# LedDuino.net
KiCad netlist of a schematic drawn in Altium Designer
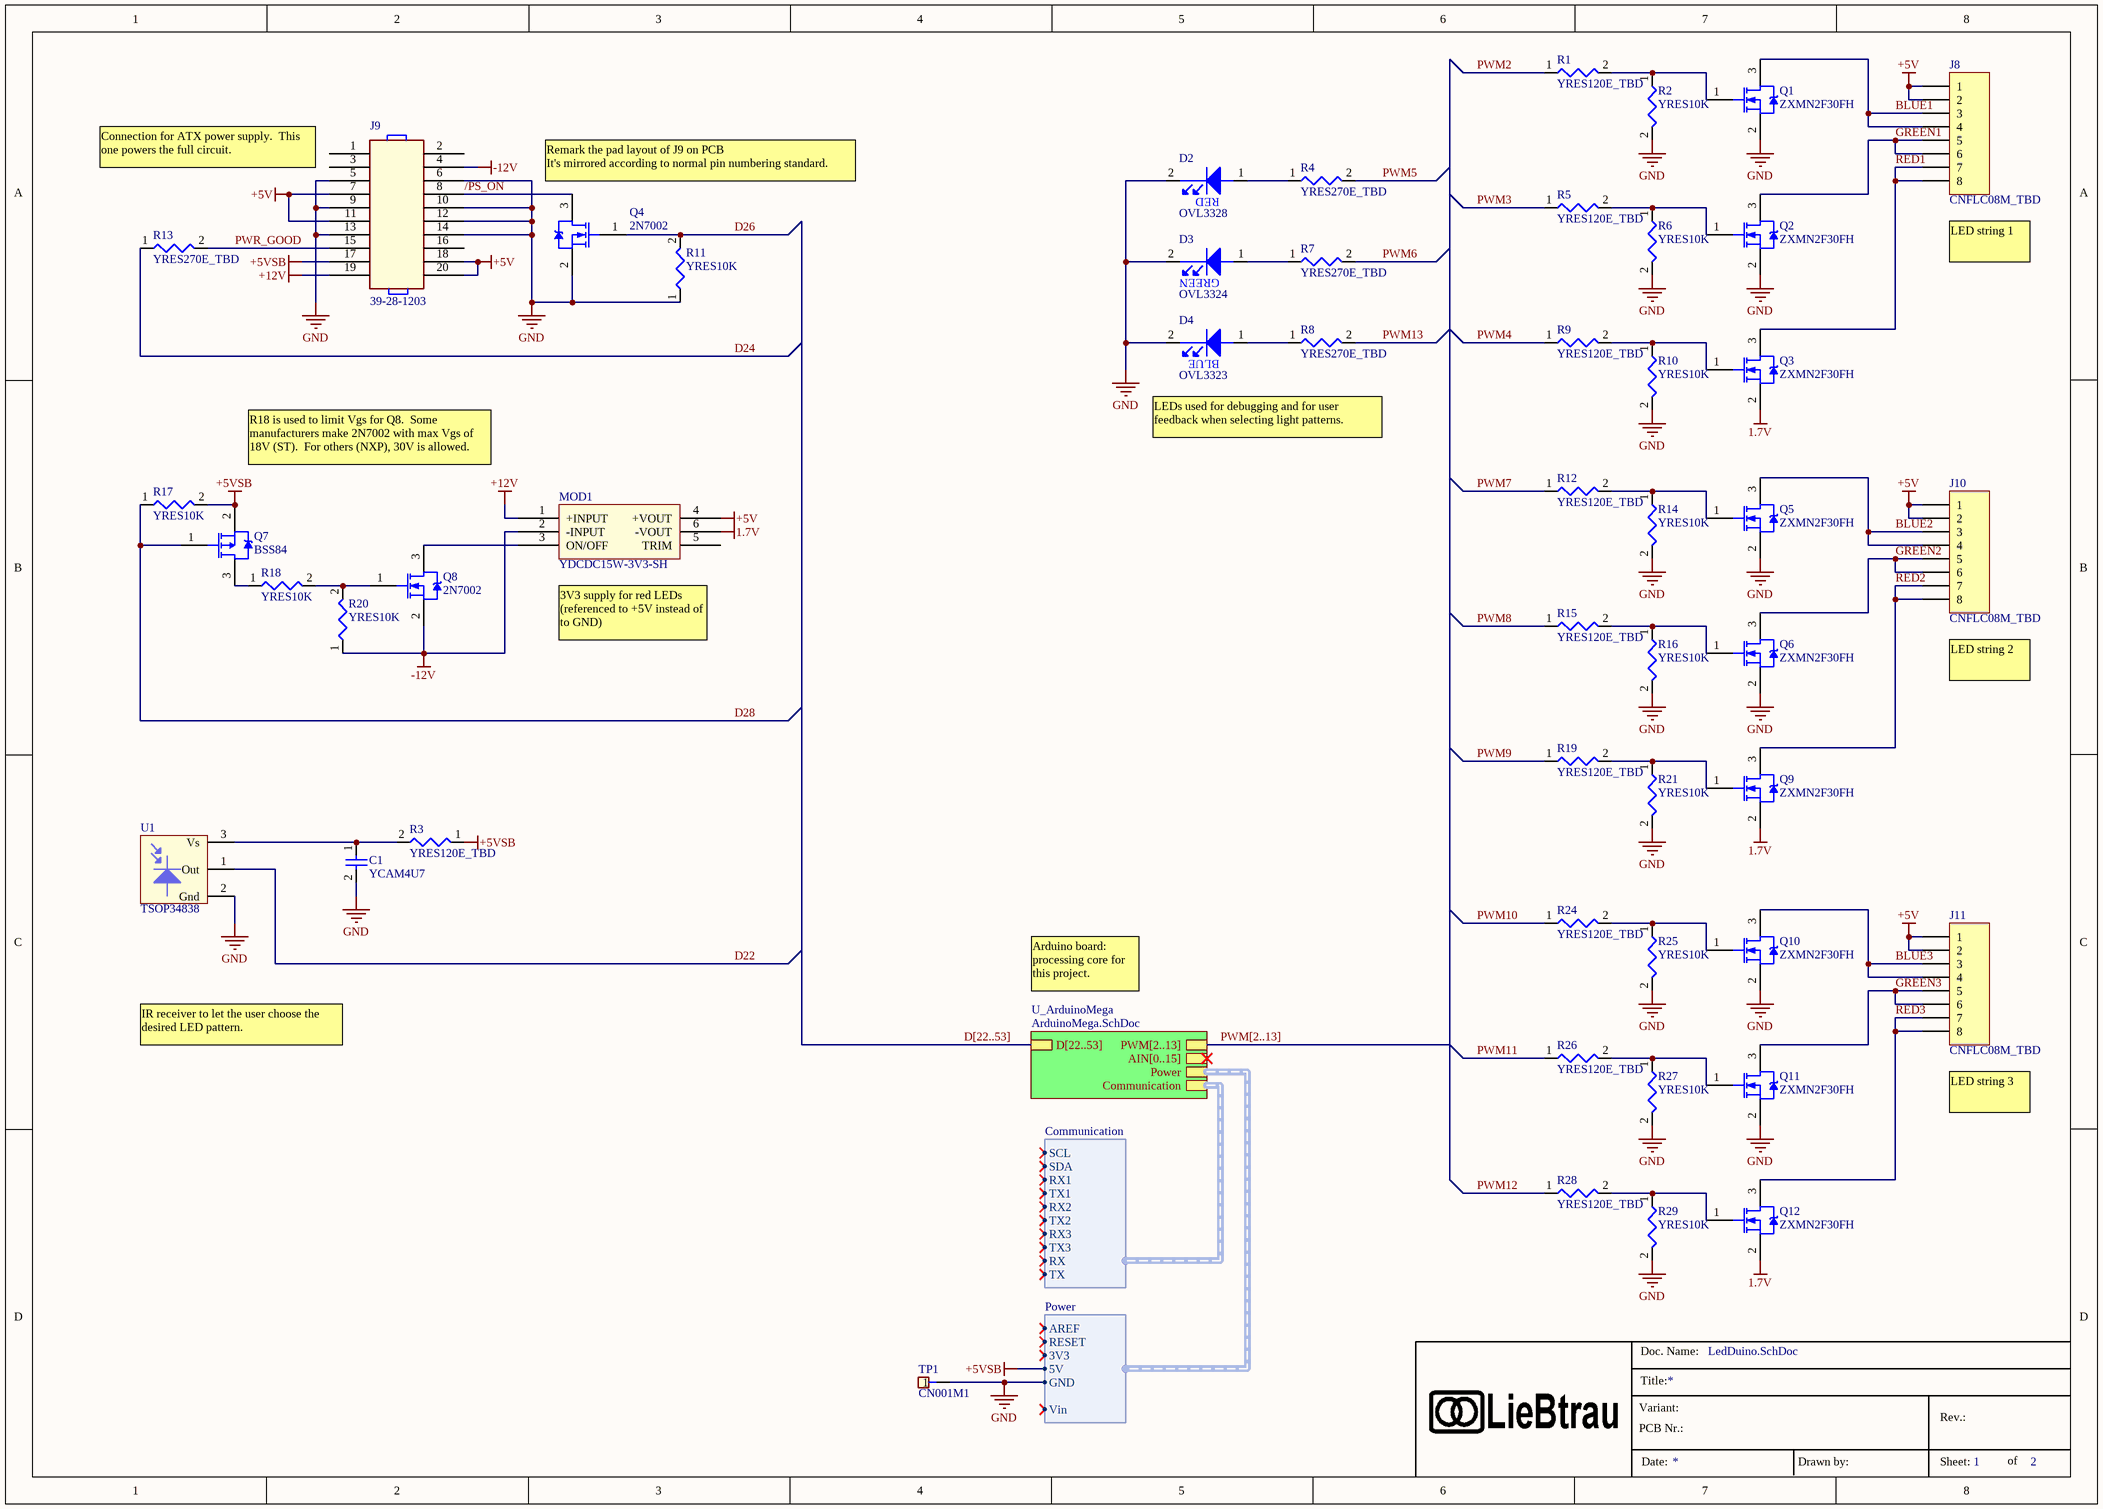
[diagram p0: LedDuino.SchDoc]

(export (version "E")
  (design (tool "Eeschema 10.0.6"))
  (components
    (comp (ref "C1") (value "YCAM4U7") (footprint "C_1206") (libsource (lib "Testing") (part "C_NONPOL")))
    (comp (ref "D2")
      (value "OVL3328")
      (footprint "D_LED3mm_straight")
      (fields (field (name "MANUFACTURER") "Multicomp"))
      (libsource (lib "Testing") (part "D_LED_RED"))
    )
    (comp (ref "D3")
      (value "OVL3324")
      (footprint "D_LED3mm_straight")
      (fields (field (name "MANUFACTURER") "Multicomp"))
      (libsource (lib "Testing") (part "D_LED_GREEN"))
    )
    (comp (ref "D4")
      (value "OVL3323")
      (footprint "D_LED3mm_straight")
      (fields (field (name "MANUFACTURER") "Multicomp"))
      (libsource (lib "Testing") (part "D_LED_BLUE"))
    )
    (comp (ref "J8")
      (value "CNFLC08M_TBD")
      (footprint "J_215079-8")
      (fields (field (name "PART NUMBER") "CNFLC08F_TBD"))
      (libsource (lib "Testing") (part "J_8P"))
    )
    (comp (ref "J9")
      (value "39-28-1203")
      (footprint "J_MiniFit_Jr_20P")
      (fields (field (name "MANUFACTURER") "Molex"))
      (libsource (lib "Testing") (part "J_2x10P"))
    )
    (comp (ref "J10")
      (value "CNFLC08M_TBD")
      (footprint "J_215079-8")
      (fields (field (name "PART NUMBER") "CNFLC08F_TBD"))
      (libsource (lib "Testing") (part "J_8P"))
    )
    (comp (ref "J11")
      (value "CNFLC08M_TBD")
      (footprint "J_215079-8")
      (fields (field (name "PART NUMBER") "CNFLC08F_TBD"))
      (libsource (lib "Testing") (part "J_8P"))
    )
    (comp (ref "MOD1")
      (value "YDCDC15W-3V3-SH")
      (footprint "MOD_DCDC_15W_TH")
      (libsource (lib "Testing") (part "MOD_DCDC_ON"))
    )
    (comp (ref "Q1")
      (value "ZXMN2F30FH")
      (footprint "SOT23")
      (fields (field (name "MANUFACTURER") "Zetex"))
      (libsource (lib "Testing") (part "Q_NMOS"))
    )
    (comp (ref "Q2")
      (value "ZXMN2F30FH")
      (footprint "SOT23")
      (fields (field (name "MANUFACTURER") "Zetex"))
      (libsource (lib "Testing") (part "Q_NMOS"))
    )
    (comp (ref "Q3")
      (value "ZXMN2F30FH")
      (footprint "SOT23")
      (fields (field (name "MANUFACTURER") "Zetex"))
      (libsource (lib "Testing") (part "Q_NMOS"))
    )
    (comp (ref "Q4") (value "2N7002") (footprint "SOT23") (libsource (lib "Testing") (part "Q_NMOS")))
    (comp (ref "Q5")
      (value "ZXMN2F30FH")
      (footprint "SOT23")
      (fields (field (name "MANUFACTURER") "Zetex"))
      (libsource (lib "Testing") (part "Q_NMOS"))
    )
    (comp (ref "Q6")
      (value "ZXMN2F30FH")
      (footprint "SOT23")
      (fields (field (name "MANUFACTURER") "Zetex"))
      (libsource (lib "Testing") (part "Q_NMOS"))
    )
    (comp (ref "Q7") (value "BSS84") (footprint "SOT23") (libsource (lib "Testing") (part "Q_PMOS")))
    (comp (ref "Q8") (value "2N7002") (footprint "SOT23") (libsource (lib "Testing") (part "Q_NMOS")))
    (comp (ref "Q9")
      (value "ZXMN2F30FH")
      (footprint "SOT23")
      (fields (field (name "MANUFACTURER") "Zetex"))
      (libsource (lib "Testing") (part "Q_NMOS"))
    )
    (comp (ref "Q10")
      (value "ZXMN2F30FH")
      (footprint "SOT23")
      (fields (field (name "MANUFACTURER") "Zetex"))
      (libsource (lib "Testing") (part "Q_NMOS"))
    )
    (comp (ref "Q11")
      (value "ZXMN2F30FH")
      (footprint "SOT23")
      (fields (field (name "MANUFACTURER") "Zetex"))
      (libsource (lib "Testing") (part "Q_NMOS"))
    )
    (comp (ref "Q12")
      (value "ZXMN2F30FH")
      (footprint "SOT23")
      (fields (field (name "MANUFACTURER") "Zetex"))
      (libsource (lib "Testing") (part "Q_NMOS"))
    )
    (comp (ref "R1")
      (value "YRES120E_TBD")
      (footprint "R_1206")
      (description "Resistor")
      (libsource (lib "Testing") (part "R_RES"))
    )
    (comp (ref "R2")
      (value "YRES10K")
      (footprint "R_1206")
      (description "Resistor")
      (libsource (lib "Testing") (part "R_RES"))
    )
    (comp (ref "R3")
      (value "YRES120E_TBD")
      (footprint "R_1206")
      (description "Resistor")
      (libsource (lib "Testing") (part "R_RES"))
    )
    (comp (ref "R4")
      (value "YRES270E_TBD")
      (footprint "R_1206")
      (description "Resistor")
      (libsource (lib "Testing") (part "R_RES"))
    )
    (comp (ref "R5")
      (value "YRES120E_TBD")
      (footprint "R_1206")
      (description "Resistor")
      (libsource (lib "Testing") (part "R_RES"))
    )
    (comp (ref "R6")
      (value "YRES10K")
      (footprint "R_1206")
      (description "Resistor")
      (libsource (lib "Testing") (part "R_RES"))
    )
    (comp (ref "R7")
      (value "YRES270E_TBD")
      (footprint "R_1206")
      (description "Resistor")
      (libsource (lib "Testing") (part "R_RES"))
    )
    (comp (ref "R8")
      (value "YRES270E_TBD")
      (footprint "R_1206")
      (description "Resistor")
      (libsource (lib "Testing") (part "R_RES"))
    )
    (comp (ref "R9")
      (value "YRES120E_TBD")
      (footprint "R_1206")
      (description "Resistor")
      (libsource (lib "Testing") (part "R_RES"))
    )
    (comp (ref "R10")
      (value "YRES10K")
      (footprint "R_1206")
      (description "Resistor")
      (libsource (lib "Testing") (part "R_RES"))
    )
    (comp (ref "R11")
      (value "YRES10K")
      (footprint "R_1206")
      (description "Resistor")
      (libsource (lib "Testing") (part "R_RES"))
    )
    (comp (ref "R12")
      (value "YRES120E_TBD")
      (footprint "R_1206")
      (description "Resistor")
      (libsource (lib "Testing") (part "R_RES"))
    )
    (comp (ref "R13")
      (value "YRES270E_TBD")
      (footprint "R_1206")
      (description "Resistor")
      (libsource (lib "Testing") (part "R_RES"))
    )
    (comp (ref "R14")
      (value "YRES10K")
      (footprint "R_1206")
      (description "Resistor")
      (libsource (lib "Testing") (part "R_RES"))
    )
    (comp (ref "R15")
      (value "YRES120E_TBD")
      (footprint "R_1206")
      (description "Resistor")
      (libsource (lib "Testing") (part "R_RES"))
    )
    (comp (ref "R16")
      (value "YRES10K")
      (footprint "R_1206")
      (description "Resistor")
      (libsource (lib "Testing") (part "R_RES"))
    )
    (comp (ref "R17")
      (value "YRES10K")
      (footprint "R_1206")
      (description "Resistor")
      (libsource (lib "Testing") (part "R_RES"))
    )
    (comp (ref "R18")
      (value "YRES10K")
      (footprint "R_1206")
      (description "Resistor")
      (libsource (lib "Testing") (part "R_RES"))
    )
    (comp (ref "R19")
      (value "YRES120E_TBD")
      (footprint "R_1206")
      (description "Resistor")
      (libsource (lib "Testing") (part "R_RES"))
    )
    (comp (ref "R20")
      (value "YRES10K")
      (footprint "R_1206")
      (description "Resistor")
      (libsource (lib "Testing") (part "R_RES"))
    )
    (comp (ref "R21")
      (value "YRES10K")
      (footprint "R_1206")
      (description "Resistor")
      (libsource (lib "Testing") (part "R_RES"))
    )
    (comp (ref "R24")
      (value "YRES120E_TBD")
      (footprint "R_1206")
      (description "Resistor")
      (libsource (lib "Testing") (part "R_RES"))
    )
    (comp (ref "R25")
      (value "YRES10K")
      (footprint "R_1206")
      (description "Resistor")
      (libsource (lib "Testing") (part "R_RES"))
    )
    (comp (ref "R26")
      (value "YRES120E_TBD")
      (footprint "R_1206")
      (description "Resistor")
      (libsource (lib "Testing") (part "R_RES"))
    )
    (comp (ref "R27")
      (value "YRES10K")
      (footprint "R_1206")
      (description "Resistor")
      (libsource (lib "Testing") (part "R_RES"))
    )
    (comp (ref "R28")
      (value "YRES120E_TBD")
      (footprint "R_1206")
      (description "Resistor")
      (libsource (lib "Testing") (part "R_RES"))
    )
    (comp (ref "R29")
      (value "YRES10K")
      (footprint "R_1206")
      (description "Resistor")
      (libsource (lib "Testing") (part "R_RES"))
    )
    (comp (ref "TP1")
      (value "CN001M1")
      (footprint "TP_TH_1.3mm")
      (libsource (lib "Testing") (part "TP_TESTPIN"))
    )
    (comp (ref "U1")
      (value "TSOP34838")
      (footprint "TSOP34XXX")
      (fields (field (name "MANUFACTURER") "Vishay"))
      (libsource (lib "Testing") (part "TSOPXXXX"))
    )
  )
  (nets
    (net (code "31") (name "+5V") (class "Default")
      (node (ref "J10") (pin "1") (pinfunction "1_1") (pintype "passive"))
      (node (ref "J10") (pin "2") (pinfunction "2_2") (pintype "passive"))
      (node (ref "J11") (pin "1") (pinfunction "1_1") (pintype "passive"))
      (node (ref "J11") (pin "2") (pinfunction "2_2") (pintype "passive"))
      (node (ref "J8") (pin "1") (pinfunction "1_1") (pintype "passive"))
      (node (ref "J8") (pin "2") (pinfunction "2_2") (pintype "passive"))
      (node (ref "J9") (pin "11") (pinfunction "11_11") (pintype "passive"))
      (node (ref "J9") (pin "18") (pinfunction "18_18") (pintype "passive"))
      (node (ref "J9") (pin "20") (pinfunction "20_20") (pintype "passive"))
      (node (ref "J9") (pin "7") (pinfunction "7_7") (pintype "passive"))
      (node (ref "MOD1") (pin "4") (pinfunction "+VOUT_4") (pintype "passive"))
    )
    (net (code "32") (name "+5VSB") (class "Default")
      (node (ref "J9") (pin "17") (pinfunction "17_17") (pintype "passive"))
      (node (ref "Q7") (pin "2") (pinfunction "S_2") (pintype "passive"))
      (node (ref "R17") (pin "2") (pinfunction "2_2") (pintype "passive"))
      (node (ref "R3") (pin "1") (pinfunction "1_1") (pintype "passive"))
    )
    (net (code "33") (name "+12V") (class "Default")
      (node (ref "J9") (pin "19") (pinfunction "19_19") (pintype "passive"))
      (node (ref "MOD1") (pin "1") (pinfunction "+INPUT_1") (pintype "passive"))
    )
    (net (code "34") (name "-12V") (class "Default")
      (node (ref "J9") (pin "4") (pinfunction "4_4") (pintype "passive"))
      (node (ref "MOD1") (pin "2") (pinfunction "-INPUT_2") (pintype "passive"))
      (node (ref "Q8") (pin "2") (pinfunction "S_2") (pintype "passive"))
      (node (ref "R20") (pin "1") (pinfunction "1_1") (pintype "passive"))
    )
    (net (code "36") (name "/BLUE1") (class "Default")
      (node (ref "J8") (pin "3") (pinfunction "3_3") (pintype "passive"))
      (node (ref "J8") (pin "4") (pinfunction "4_4") (pintype "passive"))
      (node (ref "Q1") (pin "3") (pinfunction "D_3") (pintype "passive"))
    )
    (net (code "37") (name "/BLUE2") (class "Default")
      (node (ref "J10") (pin "3") (pinfunction "3_3") (pintype "passive"))
      (node (ref "J10") (pin "4") (pinfunction "4_4") (pintype "passive"))
      (node (ref "Q5") (pin "3") (pinfunction "D_3") (pintype "passive"))
    )
    (net (code "38") (name "/BLUE3") (class "Default")
      (node (ref "J11") (pin "3") (pinfunction "3_3") (pintype "passive"))
      (node (ref "J11") (pin "4") (pinfunction "4_4") (pintype "passive"))
      (node (ref "Q10") (pin "3") (pinfunction "D_3") (pintype "passive"))
    )
    (net (code "39") (name "/D22") (class "Default")
      (node (ref "U1") (pin "1") (pinfunction "Out_1") (pintype "passive"))
    )
    (net (code "40") (name "/D24") (class "Default")
      (node (ref "R13") (pin "1") (pinfunction "1_1") (pintype "passive"))
    )
    (net (code "41") (name "/D26") (class "Default")
      (node (ref "Q4") (pin "1") (pinfunction "G_1") (pintype "passive"))
      (node (ref "R11") (pin "2") (pinfunction "2_2") (pintype "passive"))
    )
    (net (code "42") (name "/D28") (class "Default")
      (node (ref "Q7") (pin "1") (pinfunction "G_1") (pintype "passive"))
      (node (ref "R17") (pin "1") (pinfunction "1_1") (pintype "passive"))
    )
    (net (code "44") (name "/GREEN1") (class "Default")
      (node (ref "J8") (pin "5") (pinfunction "5_5") (pintype "passive"))
      (node (ref "J8") (pin "6") (pinfunction "6_6") (pintype "passive"))
      (node (ref "Q2") (pin "3") (pinfunction "D_3") (pintype "passive"))
    )
    (net (code "45") (name "/GREEN2") (class "Default")
      (node (ref "J10") (pin "5") (pinfunction "5_5") (pintype "passive"))
      (node (ref "J10") (pin "6") (pinfunction "6_6") (pintype "passive"))
      (node (ref "Q6") (pin "3") (pinfunction "D_3") (pintype "passive"))
    )
    (net (code "46") (name "/GREEN3") (class "Default")
      (node (ref "J11") (pin "5") (pinfunction "5_5") (pintype "passive"))
      (node (ref "J11") (pin "6") (pinfunction "6_6") (pintype "passive"))
      (node (ref "Q11") (pin "3") (pinfunction "D_3") (pintype "passive"))
    )
    (net (code "47") (name "/PWM2") (class "Default")
      (node (ref "R1") (pin "1") (pinfunction "1_1") (pintype "passive"))
    )
    (net (code "48") (name "/PWM3") (class "Default")
      (node (ref "R5") (pin "1") (pinfunction "1_1") (pintype "passive"))
    )
    (net (code "49") (name "/PWM4") (class "Default")
      (node (ref "R9") (pin "1") (pinfunction "1_1") (pintype "passive"))
    )
    (net (code "50") (name "/PWM5") (class "Default")
      (node (ref "R4") (pin "2") (pinfunction "2_2") (pintype "passive"))
    )
    (net (code "51") (name "/PWM6") (class "Default")
      (node (ref "R7") (pin "2") (pinfunction "2_2") (pintype "passive"))
    )
    (net (code "52") (name "/PWM7") (class "Default")
      (node (ref "R12") (pin "1") (pinfunction "1_1") (pintype "passive"))
    )
    (net (code "53") (name "/PWM8") (class "Default")
      (node (ref "R15") (pin "1") (pinfunction "1_1") (pintype "passive"))
    )
    (net (code "54") (name "/PWM9") (class "Default")
      (node (ref "R19") (pin "1") (pinfunction "1_1") (pintype "passive"))
    )
    (net (code "55") (name "/PWM10") (class "Default")
      (node (ref "R24") (pin "1") (pinfunction "1_1") (pintype "passive"))
    )
    (net (code "56") (name "/PWM11") (class "Default")
      (node (ref "R26") (pin "1") (pinfunction "1_1") (pintype "passive"))
    )
    (net (code "57") (name "/PWM12") (class "Default")
      (node (ref "R28") (pin "1") (pinfunction "1_1") (pintype "passive"))
    )
    (net (code "58") (name "/PWM13") (class "Default")
      (node (ref "R8") (pin "2") (pinfunction "2_2") (pintype "passive"))
    )
    (net (code "60") (name "/PWR_GOOD") (class "Default")
      (node (ref "J9") (pin "15") (pinfunction "15_15") (pintype "passive"))
      (node (ref "R13") (pin "2") (pinfunction "2_2") (pintype "passive"))
    )
    (net (code "61") (name "/RED1") (class "Default")
      (node (ref "J8") (pin "7") (pinfunction "7_7") (pintype "passive"))
      (node (ref "J8") (pin "8") (pinfunction "8_8") (pintype "passive"))
      (node (ref "Q3") (pin "3") (pinfunction "D_3") (pintype "passive"))
    )
    (net (code "62") (name "/RED2") (class "Default")
      (node (ref "J10") (pin "7") (pinfunction "7_7") (pintype "passive"))
      (node (ref "J10") (pin "8") (pinfunction "8_8") (pintype "passive"))
      (node (ref "Q9") (pin "3") (pinfunction "D_3") (pintype "passive"))
    )
    (net (code "63") (name "/RED3") (class "Default")
      (node (ref "J11") (pin "7") (pinfunction "7_7") (pintype "passive"))
      (node (ref "J11") (pin "8") (pinfunction "8_8") (pintype "passive"))
      (node (ref "Q12") (pin "3") (pinfunction "D_3") (pintype "passive"))
    )
    (net (code "66") (name "/{slash}PS_ON") (class "Default")
      (node (ref "J9") (pin "8") (pinfunction "8_8") (pintype "passive"))
      (node (ref "Q4") (pin "3") (pinfunction "D_3") (pintype "passive"))
    )
    (net (code "67") (name "1.7V") (class "Default")
      (node (ref "MOD1") (pin "6") (pinfunction "-VOUT_6") (pintype "passive"))
      (node (ref "Q12") (pin "2") (pinfunction "S_2") (pintype "passive"))
      (node (ref "Q3") (pin "2") (pinfunction "S_2") (pintype "passive"))
      (node (ref "Q9") (pin "2") (pinfunction "S_2") (pintype "passive"))
    )
    (net (code "68") (name "GND") (class "Default")
      (node (ref "C1") (pin "2") (pinfunction "2_2") (pintype "passive"))
      (node (ref "D2") (pin "2") (pinfunction "C_2") (pintype "passive"))
      (node (ref "D3") (pin "2") (pinfunction "C_2") (pintype "passive"))
      (node (ref "D4") (pin "2") (pinfunction "C_2") (pintype "passive"))
      (node (ref "J9") (pin "10") (pinfunction "10_10") (pintype "passive"))
      (node (ref "J9") (pin "12") (pinfunction "12_12") (pintype "passive"))
      (node (ref "J9") (pin "13") (pinfunction "13_13") (pintype "passive"))
      (node (ref "J9") (pin "14") (pinfunction "14_14") (pintype "passive"))
      (node (ref "J9") (pin "5") (pinfunction "5_5") (pintype "passive"))
      (node (ref "J9") (pin "6") (pinfunction "6_6") (pintype "passive"))
      (node (ref "J9") (pin "9") (pinfunction "9_9") (pintype "passive"))
      (node (ref "Q1") (pin "2") (pinfunction "S_2") (pintype "passive"))
      (node (ref "Q10") (pin "2") (pinfunction "S_2") (pintype "passive"))
      (node (ref "Q11") (pin "2") (pinfunction "S_2") (pintype "passive"))
      (node (ref "Q2") (pin "2") (pinfunction "S_2") (pintype "passive"))
      (node (ref "Q4") (pin "2") (pinfunction "S_2") (pintype "passive"))
      (node (ref "Q5") (pin "2") (pinfunction "S_2") (pintype "passive"))
      (node (ref "Q6") (pin "2") (pinfunction "S_2") (pintype "passive"))
      (node (ref "R10") (pin "2") (pinfunction "2_2") (pintype "passive"))
      (node (ref "R11") (pin "1") (pinfunction "1_1") (pintype "passive"))
      (node (ref "R14") (pin "2") (pinfunction "2_2") (pintype "passive"))
      (node (ref "R16") (pin "2") (pinfunction "2_2") (pintype "passive"))
      (node (ref "R2") (pin "2") (pinfunction "2_2") (pintype "passive"))
      (node (ref "R21") (pin "2") (pinfunction "2_2") (pintype "passive"))
      (node (ref "R25") (pin "2") (pinfunction "2_2") (pintype "passive"))
      (node (ref "R27") (pin "2") (pinfunction "2_2") (pintype "passive"))
      (node (ref "R29") (pin "2") (pinfunction "2_2") (pintype "passive"))
      (node (ref "R6") (pin "2") (pinfunction "2_2") (pintype "passive"))
      (node (ref "TP1") (pin "1") (pinfunction "1_1") (pintype "passive"))
      (node (ref "U1") (pin "2") (pinfunction "Gnd_2") (pintype "passive"))
    )
    (net (code "69") (name "Net-(D2-A)") (class "Default")
      (node (ref "D2") (pin "1") (pinfunction "A_1") (pintype "passive"))
      (node (ref "R4") (pin "1") (pinfunction "1_1") (pintype "passive"))
    )
    (net (code "70") (name "Net-(D3-A)") (class "Default")
      (node (ref "D3") (pin "1") (pinfunction "A_1") (pintype "passive"))
      (node (ref "R7") (pin "1") (pinfunction "1_1") (pintype "passive"))
    )
    (net (code "71") (name "Net-(D4-A)") (class "Default")
      (node (ref "D4") (pin "1") (pinfunction "A_1") (pintype "passive"))
      (node (ref "R8") (pin "1") (pinfunction "1_1") (pintype "passive"))
    )
    (net (code "72") (name "Net-(MOD1-ON{slash}OFF)") (class "Default")
      (node (ref "MOD1") (pin "3") (pinfunction "ON/OFF_3") (pintype "passive"))
      (node (ref "Q8") (pin "3") (pinfunction "D_3") (pintype "passive"))
    )
    (net (code "73") (name "Net-(Q1-G)") (class "Default")
      (node (ref "Q1") (pin "1") (pinfunction "G_1") (pintype "passive"))
      (node (ref "R1") (pin "2") (pinfunction "2_2") (pintype "passive"))
      (node (ref "R2") (pin "1") (pinfunction "1_1") (pintype "passive"))
    )
    (net (code "74") (name "Net-(Q2-G)") (class "Default")
      (node (ref "Q2") (pin "1") (pinfunction "G_1") (pintype "passive"))
      (node (ref "R5") (pin "2") (pinfunction "2_2") (pintype "passive"))
      (node (ref "R6") (pin "1") (pinfunction "1_1") (pintype "passive"))
    )
    (net (code "75") (name "Net-(Q3-G)") (class "Default")
      (node (ref "Q3") (pin "1") (pinfunction "G_1") (pintype "passive"))
      (node (ref "R10") (pin "1") (pinfunction "1_1") (pintype "passive"))
      (node (ref "R9") (pin "2") (pinfunction "2_2") (pintype "passive"))
    )
    (net (code "76") (name "Net-(Q5-G)") (class "Default")
      (node (ref "Q5") (pin "1") (pinfunction "G_1") (pintype "passive"))
      (node (ref "R12") (pin "2") (pinfunction "2_2") (pintype "passive"))
      (node (ref "R14") (pin "1") (pinfunction "1_1") (pintype "passive"))
    )
    (net (code "77") (name "Net-(Q6-G)") (class "Default")
      (node (ref "Q6") (pin "1") (pinfunction "G_1") (pintype "passive"))
      (node (ref "R15") (pin "2") (pinfunction "2_2") (pintype "passive"))
      (node (ref "R16") (pin "1") (pinfunction "1_1") (pintype "passive"))
    )
    (net (code "78") (name "Net-(Q7-D)") (class "Default")
      (node (ref "Q7") (pin "3") (pinfunction "D_3") (pintype "passive"))
      (node (ref "R18") (pin "1") (pinfunction "1_1") (pintype "passive"))
    )
    (net (code "79") (name "Net-(Q8-G)") (class "Default")
      (node (ref "Q8") (pin "1") (pinfunction "G_1") (pintype "passive"))
      (node (ref "R18") (pin "2") (pinfunction "2_2") (pintype "passive"))
      (node (ref "R20") (pin "2") (pinfunction "2_2") (pintype "passive"))
    )
    (net (code "80") (name "Net-(Q9-G)") (class "Default")
      (node (ref "Q9") (pin "1") (pinfunction "G_1") (pintype "passive"))
      (node (ref "R19") (pin "2") (pinfunction "2_2") (pintype "passive"))
      (node (ref "R21") (pin "1") (pinfunction "1_1") (pintype "passive"))
    )
    (net (code "81") (name "Net-(Q10-G)") (class "Default")
      (node (ref "Q10") (pin "1") (pinfunction "G_1") (pintype "passive"))
      (node (ref "R24") (pin "2") (pinfunction "2_2") (pintype "passive"))
      (node (ref "R25") (pin "1") (pinfunction "1_1") (pintype "passive"))
    )
    (net (code "82") (name "Net-(Q11-G)") (class "Default")
      (node (ref "Q11") (pin "1") (pinfunction "G_1") (pintype "passive"))
      (node (ref "R26") (pin "2") (pinfunction "2_2") (pintype "passive"))
      (node (ref "R27") (pin "1") (pinfunction "1_1") (pintype "passive"))
    )
    (net (code "83") (name "Net-(Q12-G)") (class "Default")
      (node (ref "Q12") (pin "1") (pinfunction "G_1") (pintype "passive"))
      (node (ref "R28") (pin "2") (pinfunction "2_2") (pintype "passive"))
      (node (ref "R29") (pin "1") (pinfunction "1_1") (pintype "passive"))
    )
    (net (code "84") (name "Net-(U1-Vs)") (class "Default")
      (node (ref "C1") (pin "1") (pinfunction "1_1") (pintype "passive"))
      (node (ref "R3") (pin "2") (pinfunction "2_2") (pintype "passive"))
      (node (ref "U1") (pin "3") (pinfunction "Vs_3") (pintype "passive"))
    )
    (net (code "85") (name "unconnected-(J9-Pad1)") (class "Default")
      (node (ref "J9") (pin "1") (pinfunction "1_1") (pintype "passive"))
    )
    (net (code "86") (name "unconnected-(J9-Pad2)") (class "Default")
      (node (ref "J9") (pin "2") (pinfunction "2_2") (pintype "passive"))
    )
    (net (code "87") (name "unconnected-(J9-Pad3)") (class "Default")
      (node (ref "J9") (pin "3") (pinfunction "3_3") (pintype "passive"))
    )
    (net (code "88") (name "unconnected-(J9-Pad16)") (class "Default")
      (node (ref "J9") (pin "16") (pinfunction "16_16") (pintype "passive"))
    )
    (net (code "89") (name "unconnected-(MOD1-TRIM-Pad5)") (class "Default")
      (node (ref "MOD1") (pin "5") (pinfunction "TRIM_5") (pintype "passive"))
    )
  )
)
